# 119_03_INTELLIGENT_SENSOR_BOARD_816.net
KiCad netlist of a schematic drawn in EAGLE
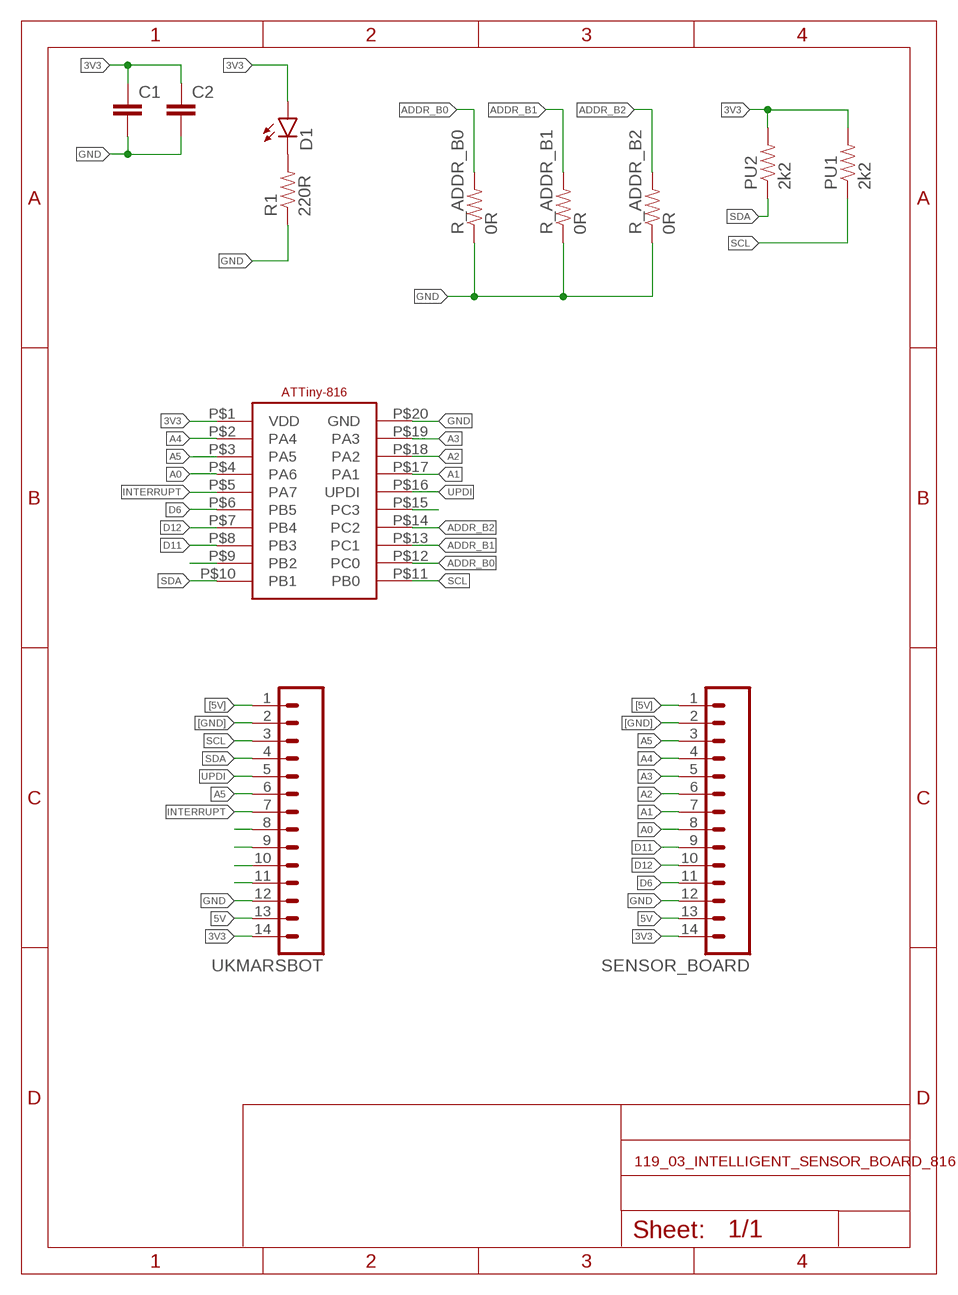
[diagram p0: schematic, sheet 1]

(export (version "E")
  (design (tool "Eeschema 10.0.6"))
  (components
    (comp (ref "C1")
      (value "CAP0805")
      (footprint "eagle-import:0805")
      (libsource (lib "eagle-import") (part "CAP0805"))
    )
    (comp (ref "C2")
      (value "CAP0805")
      (footprint "eagle-import:0805")
      (libsource (lib "eagle-import") (part "CAP0805"))
    )
    (comp (ref "D1")
      (value "LEDCHIP-LED0805")
      (footprint "eagle-import:CHIP-LED0805")
      (libsource (lib "eagle-import") (part "LEDCHIP-LED0805"))
    )
    (comp (ref "PU1")
      (value "2k2")
      (footprint "eagle-import:0805")
      (libsource (lib "eagle-import") (part "RESISTOR0805-RES"))
    )
    (comp (ref "PU2")
      (value "2k2")
      (footprint "eagle-import:0805")
      (libsource (lib "eagle-import") (part "RESISTOR0805-RES"))
    )
    (comp (ref "R1")
      (value "220R")
      (footprint "eagle-import:0805")
      (libsource (lib "eagle-import") (part "RESISTOR0805-RES"))
    )
    (comp (ref "R_ADDR_B0")
      (value "0R")
      (footprint "eagle-import:0805")
      (libsource (lib "eagle-import") (part "RESISTOR0805-RES"))
    )
    (comp (ref "R_ADDR_B1")
      (value "0R")
      (footprint "eagle-import:0805")
      (libsource (lib "eagle-import") (part "RESISTOR0805-RES"))
    )
    (comp (ref "R_ADDR_B2")
      (value "0R")
      (footprint "eagle-import:0805")
      (libsource (lib "eagle-import") (part "RESISTOR0805-RES"))
    )
    (comp (ref "SENSOR_BOARD")
      (value "M14")
      (footprint "eagle-import:14P")
      (libsource (lib "eagle-import") (part "M14"))
    )
    (comp (ref "U$2")
      (value "ATTINY816")
      (footprint "eagle-import:ATTINY816_SOIC20")
      (libsource (lib "eagle-import") (part "ATTINY816"))
    )
    (comp (ref "UKMARSBOT")
      (value "M14")
      (footprint "eagle-import:14P")
      (libsource (lib "eagle-import") (part "M14"))
    )
  )
  (nets
    (net (code "1") (name "3V3") (class "Default")
      (node (ref "C1") (pin "1") (pinfunction "1_1") (pintype "passive"))
      (node (ref "C2") (pin "1") (pinfunction "1_1") (pintype "passive"))
      (node (ref "D1") (pin "A") (pinfunction "A_A") (pintype "passive"))
      (node (ref "PU1") (pin "2") (pinfunction "2_2") (pintype "passive"))
      (node (ref "PU2") (pin "2") (pinfunction "2_2") (pintype "passive"))
      (node (ref "SENSOR_BOARD") (pin "14") (pinfunction "14_14") (pintype "passive"))
      (node (ref "U$2") (pin "P$1") (pinfunction "VDD_P$1") (pintype "bidirectional"))
      (node (ref "UKMARSBOT") (pin "14") (pinfunction "14_14") (pintype "passive"))
    )
    (net (code "2") (name "5V") (class "Default")
      (node (ref "SENSOR_BOARD") (pin "13") (pinfunction "13_13") (pintype "passive"))
      (node (ref "UKMARSBOT") (pin "13") (pinfunction "13_13") (pintype "passive"))
    )
    (net (code "3") (name "A0") (class "Default")
      (node (ref "SENSOR_BOARD") (pin "8") (pinfunction "8_8") (pintype "passive"))
      (node (ref "U$2") (pin "P$4") (pinfunction "PA6_P$4") (pintype "bidirectional"))
    )
    (net (code "4") (name "A1") (class "Default")
      (node (ref "SENSOR_BOARD") (pin "7") (pinfunction "7_7") (pintype "passive"))
      (node (ref "U$2") (pin "P$17") (pinfunction "PA1_P$17") (pintype "bidirectional"))
    )
    (net (code "5") (name "A2") (class "Default")
      (node (ref "SENSOR_BOARD") (pin "6") (pinfunction "6_6") (pintype "passive"))
      (node (ref "U$2") (pin "P$18") (pinfunction "PA2_P$18") (pintype "bidirectional"))
    )
    (net (code "6") (name "A3") (class "Default")
      (node (ref "SENSOR_BOARD") (pin "5") (pinfunction "5_5") (pintype "passive"))
      (node (ref "U$2") (pin "P$19") (pinfunction "PA3_P$19") (pintype "bidirectional"))
    )
    (net (code "7") (name "A4") (class "Default")
      (node (ref "SENSOR_BOARD") (pin "4") (pinfunction "4_4") (pintype "passive"))
      (node (ref "U$2") (pin "P$2") (pinfunction "PA4_P$2") (pintype "bidirectional"))
    )
    (net (code "8") (name "A5") (class "Default")
      (node (ref "SENSOR_BOARD") (pin "3") (pinfunction "3_3") (pintype "passive"))
      (node (ref "U$2") (pin "P$3") (pinfunction "PA5_P$3") (pintype "bidirectional"))
      (node (ref "UKMARSBOT") (pin "6") (pinfunction "6_6") (pintype "passive"))
    )
    (net (code "9") (name "ADDR_B0") (class "Default")
      (node (ref "R_ADDR_B0") (pin "2") (pinfunction "2_2") (pintype "passive"))
      (node (ref "U$2") (pin "P$12") (pinfunction "PC0_P$12") (pintype "bidirectional"))
    )
    (net (code "10") (name "ADDR_B1") (class "Default")
      (node (ref "R_ADDR_B1") (pin "2") (pinfunction "2_2") (pintype "passive"))
      (node (ref "U$2") (pin "P$13") (pinfunction "PC1_P$13") (pintype "bidirectional"))
    )
    (net (code "11") (name "ADDR_B2") (class "Default")
      (node (ref "R_ADDR_B2") (pin "2") (pinfunction "2_2") (pintype "passive"))
      (node (ref "U$2") (pin "P$14") (pinfunction "PC2_P$14") (pintype "bidirectional"))
    )
    (net (code "12") (name "D6") (class "Default")
      (node (ref "SENSOR_BOARD") (pin "11") (pinfunction "11_11") (pintype "passive"))
      (node (ref "U$2") (pin "P$6") (pinfunction "PB5_P$6") (pintype "bidirectional"))
    )
    (net (code "13") (name "D11") (class "Default")
      (node (ref "SENSOR_BOARD") (pin "9") (pinfunction "9_9") (pintype "passive"))
      (node (ref "U$2") (pin "P$8") (pinfunction "PB3_P$8") (pintype "bidirectional"))
    )
    (net (code "14") (name "D12") (class "Default")
      (node (ref "SENSOR_BOARD") (pin "10") (pinfunction "10_10") (pintype "passive"))
      (node (ref "U$2") (pin "P$7") (pinfunction "PB4_P$7") (pintype "bidirectional"))
    )
    (net (code "15") (name "GND") (class "Default")
      (node (ref "C1") (pin "2") (pinfunction "2_2") (pintype "passive"))
      (node (ref "C2") (pin "2") (pinfunction "2_2") (pintype "passive"))
      (node (ref "R1") (pin "1") (pinfunction "1_1") (pintype "passive"))
      (node (ref "R_ADDR_B0") (pin "1") (pinfunction "1_1") (pintype "passive"))
      (node (ref "R_ADDR_B1") (pin "1") (pinfunction "1_1") (pintype "passive"))
      (node (ref "R_ADDR_B2") (pin "1") (pinfunction "1_1") (pintype "passive"))
      (node (ref "SENSOR_BOARD") (pin "12") (pinfunction "12_12") (pintype "passive"))
      (node (ref "U$2") (pin "P$20") (pinfunction "GND_P$20") (pintype "bidirectional"))
      (node (ref "UKMARSBOT") (pin "12") (pinfunction "12_12") (pintype "passive"))
    )
    (net (code "16") (name "INTERRUPT") (class "Default")
      (node (ref "U$2") (pin "P$5") (pinfunction "PA7_P$5") (pintype "bidirectional"))
      (node (ref "UKMARSBOT") (pin "7") (pinfunction "7_7") (pintype "passive"))
    )
    (net (code "17") (name "Net-(D1-PadC)") (class "Default")
      (node (ref "D1") (pin "C") (pinfunction "C_C") (pintype "passive"))
      (node (ref "R1") (pin "2") (pinfunction "2_2") (pintype "passive"))
    )
    (net (code "18") (name "SCL") (class "Default")
      (node (ref "PU1") (pin "1") (pinfunction "1_1") (pintype "passive"))
      (node (ref "U$2") (pin "P$11") (pinfunction "PB0_P$11") (pintype "bidirectional"))
      (node (ref "UKMARSBOT") (pin "3") (pinfunction "3_3") (pintype "passive"))
    )
    (net (code "19") (name "SDA") (class "Default")
      (node (ref "PU2") (pin "1") (pinfunction "1_1") (pintype "passive"))
      (node (ref "U$2") (pin "P$10") (pinfunction "PB1_P$10") (pintype "bidirectional"))
      (node (ref "UKMARSBOT") (pin "4") (pinfunction "4_4") (pintype "passive"))
    )
    (net (code "20") (name "UPDI") (class "Default")
      (node (ref "U$2") (pin "P$16") (pinfunction "UPDI_P$16") (pintype "bidirectional"))
      (node (ref "UKMARSBOT") (pin "5") (pinfunction "5_5") (pintype "passive"))
    )
    (net (code "21") (name "[5V]") (class "Default")
      (node (ref "SENSOR_BOARD") (pin "1") (pinfunction "1_1") (pintype "passive"))
      (node (ref "UKMARSBOT") (pin "1") (pinfunction "1_1") (pintype "passive"))
    )
    (net (code "22") (name "[GND]") (class "Default")
      (node (ref "SENSOR_BOARD") (pin "2") (pinfunction "2_2") (pintype "passive"))
      (node (ref "UKMARSBOT") (pin "2") (pinfunction "2_2") (pintype "passive"))
    )
    (net (code "23") (name "unconnected-(U$2-PB2-PadP$9)") (class "Default")
      (node (ref "U$2") (pin "P$9") (pinfunction "PB2_P$9") (pintype "bidirectional"))
    )
    (net (code "24") (name "unconnected-(U$2-PC3-PadP$15)") (class "Default")
      (node (ref "U$2") (pin "P$15") (pinfunction "PC3_P$15") (pintype "bidirectional"))
    )
    (net (code "25") (name "unconnected-(UKMARSBOT-Pad8)") (class "Default")
      (node (ref "UKMARSBOT") (pin "8") (pinfunction "8_8") (pintype "passive"))
    )
    (net (code "26") (name "unconnected-(UKMARSBOT-Pad9)") (class "Default")
      (node (ref "UKMARSBOT") (pin "9") (pinfunction "9_9") (pintype "passive"))
    )
    (net (code "27") (name "unconnected-(UKMARSBOT-Pad10)") (class "Default")
      (node (ref "UKMARSBOT") (pin "10") (pinfunction "10_10") (pintype "passive"))
    )
    (net (code "28") (name "unconnected-(UKMARSBOT-Pad11)") (class "Default")
      (node (ref "UKMARSBOT") (pin "11") (pinfunction "11_11") (pintype "passive"))
    )
  )
)
